# xmega-flash.net
KiCad netlist of a schematic drawn in EAGLE
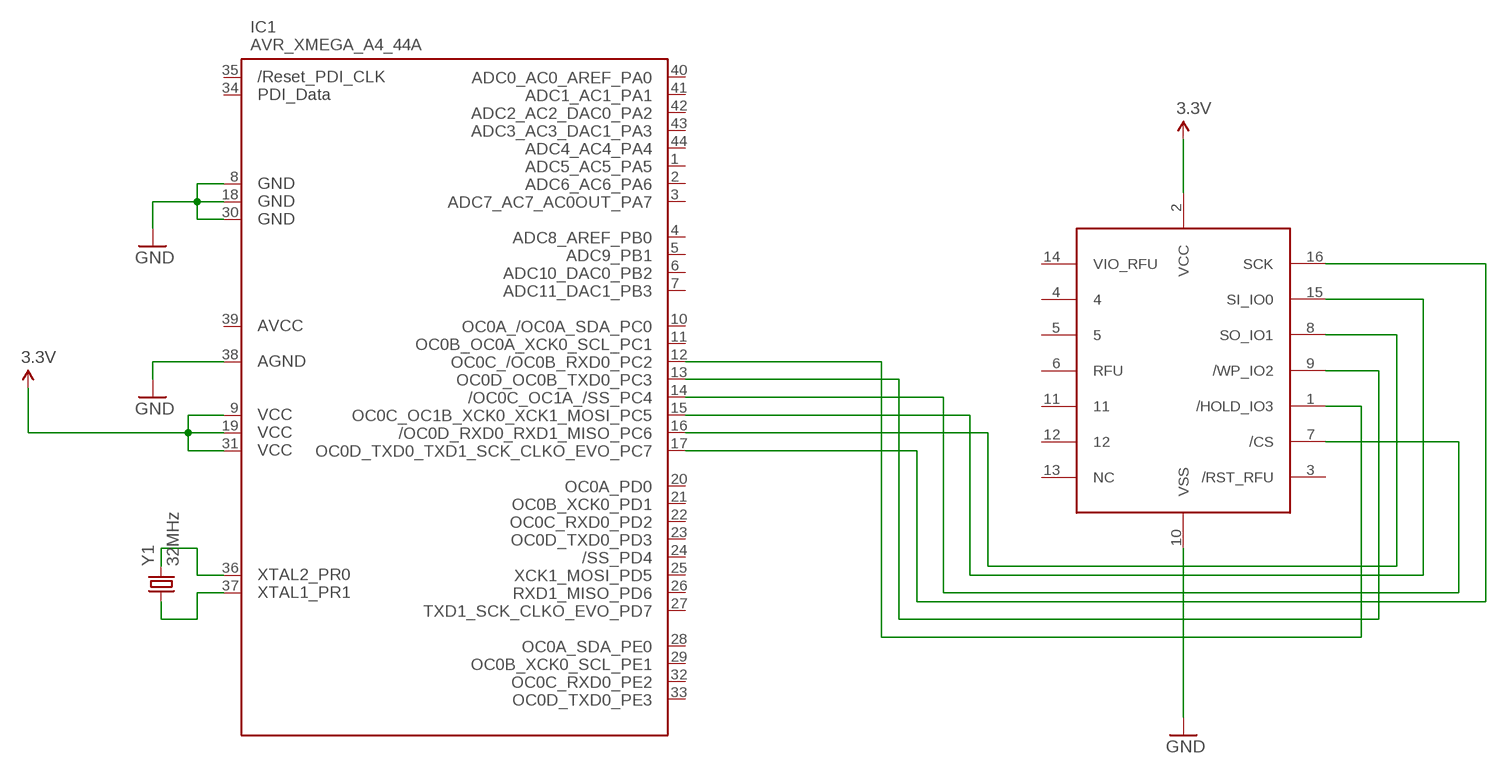
[diagram p0: schematic, sheet 1]

(export (version "E")
  (design (tool "Eeschema 10.0.6"))
  (components
    (comp (ref "IC1")
      (value "AVR_XMEGA_A4_44A")
      (footprint "eagle-import:TQFP44")
      (libsource (lib "eagle-import") (part "AVR_XMEGA_A4_44A"))
    )
    (comp (ref "U$1")
      (value "S25FLS256")
      (footprint "eagle-import:WSOIC-16")
      (libsource (lib "eagle-import") (part "S25FLS256"))
    )
    (comp (ref "Y1")
      (value "32MHz")
      (footprint "eagle-import:CRYSTAL-SMD-5X3")
      (libsource (lib "eagle-import") (part "CRYSTAL5X3"))
    )
  )
  (nets
    (net (code "1") (name "3.3V") (class "Default")
      (node (ref "IC1") (pin "19") (pinfunction "VCC2_19") (pintype "bidirectional"))
      (node (ref "IC1") (pin "31") (pinfunction "VCC3_31") (pintype "bidirectional"))
      (node (ref "IC1") (pin "9") (pinfunction "VCC1_9") (pintype "bidirectional"))
      (node (ref "U$1") (pin "2") (pinfunction "VCC_2") (pintype "bidirectional"))
    )
    (net (code "2") (name "GND") (class "Default")
      (node (ref "IC1") (pin "18") (pinfunction "GND2_18") (pintype "bidirectional"))
      (node (ref "IC1") (pin "30") (pinfunction "GND3_30") (pintype "bidirectional"))
      (node (ref "IC1") (pin "38") (pinfunction "AGND_38") (pintype "bidirectional"))
      (node (ref "IC1") (pin "8") (pinfunction "GND1_8") (pintype "bidirectional"))
      (node (ref "U$1") (pin "10") (pinfunction "VSS_10") (pintype "bidirectional"))
    )
    (net (code "3") (name "Net-(IC1-PC2)") (class "Default")
      (node (ref "IC1") (pin "12") (pinfunction "PC2_12") (pintype "bidirectional"))
      (node (ref "U$1") (pin "1") (pinfunction "/HOLD_IO3_1") (pintype "bidirectional"))
    )
    (net (code "4") (name "Net-(IC1-PC3)") (class "Default")
      (node (ref "IC1") (pin "13") (pinfunction "PC3_13") (pintype "bidirectional"))
      (node (ref "U$1") (pin "9") (pinfunction "/WP_IO2_9") (pintype "bidirectional"))
    )
    (net (code "5") (name "Net-(IC1-PC4)") (class "Default")
      (node (ref "IC1") (pin "14") (pinfunction "PC4_14") (pintype "bidirectional"))
      (node (ref "U$1") (pin "7") (pinfunction "/CS_7") (pintype "bidirectional"))
    )
    (net (code "6") (name "Net-(IC1-PC5)") (class "Default")
      (node (ref "IC1") (pin "15") (pinfunction "PC5_15") (pintype "bidirectional"))
      (node (ref "U$1") (pin "15") (pinfunction "SI_IO0_15") (pintype "bidirectional"))
    )
    (net (code "7") (name "Net-(IC1-PC6)") (class "Default")
      (node (ref "IC1") (pin "16") (pinfunction "PC6_16") (pintype "bidirectional"))
      (node (ref "U$1") (pin "8") (pinfunction "SO_IO1_8") (pintype "bidirectional"))
    )
    (net (code "8") (name "Net-(IC1-PC7)") (class "Default")
      (node (ref "IC1") (pin "17") (pinfunction "PC7_17") (pintype "bidirectional"))
      (node (ref "U$1") (pin "16") (pinfunction "SCK_16") (pintype "bidirectional"))
    )
    (net (code "9") (name "Net-(IC1-PR0)") (class "Default")
      (node (ref "IC1") (pin "36") (pinfunction "PR0_36") (pintype "bidirectional"))
      (node (ref "Y1") (pin "3") (pinfunction "2_3") (pintype "passive"))
    )
    (net (code "10") (name "Net-(IC1-PR1)") (class "Default")
      (node (ref "IC1") (pin "37") (pinfunction "PR1_37") (pintype "bidirectional"))
      (node (ref "Y1") (pin "1") (pinfunction "1_1") (pintype "passive"))
    )
    (net (code "11") (name "unconnected-(IC1-AVCC-Pad39)") (class "Default")
      (node (ref "IC1") (pin "39") (pinfunction "AVCC_39") (pintype "bidirectional"))
    )
    (net (code "12") (name "unconnected-(IC1-PA0-Pad40)") (class "Default")
      (node (ref "IC1") (pin "40") (pinfunction "PA0_40") (pintype "bidirectional"))
    )
    (net (code "13") (name "unconnected-(IC1-PA1-Pad41)") (class "Default")
      (node (ref "IC1") (pin "41") (pinfunction "PA1_41") (pintype "bidirectional"))
    )
    (net (code "14") (name "unconnected-(IC1-PA2-Pad42)") (class "Default")
      (node (ref "IC1") (pin "42") (pinfunction "PA2_42") (pintype "bidirectional"))
    )
    (net (code "15") (name "unconnected-(IC1-PA3-Pad43)") (class "Default")
      (node (ref "IC1") (pin "43") (pinfunction "PA3_43") (pintype "bidirectional"))
    )
    (net (code "16") (name "unconnected-(IC1-PA4-Pad44)") (class "Default")
      (node (ref "IC1") (pin "44") (pinfunction "PA4_44") (pintype "bidirectional"))
    )
    (net (code "17") (name "unconnected-(IC1-PA5-Pad1)") (class "Default")
      (node (ref "IC1") (pin "1") (pinfunction "PA5_1") (pintype "bidirectional"))
    )
    (net (code "18") (name "unconnected-(IC1-PA6-Pad2)") (class "Default")
      (node (ref "IC1") (pin "2") (pinfunction "PA6_2") (pintype "bidirectional"))
    )
    (net (code "19") (name "unconnected-(IC1-PA7-Pad3)") (class "Default")
      (node (ref "IC1") (pin "3") (pinfunction "PA7_3") (pintype "bidirectional"))
    )
    (net (code "20") (name "unconnected-(IC1-PB0-Pad4)") (class "Default")
      (node (ref "IC1") (pin "4") (pinfunction "PB0_4") (pintype "bidirectional"))
    )
    (net (code "21") (name "unconnected-(IC1-PB1-Pad5)") (class "Default")
      (node (ref "IC1") (pin "5") (pinfunction "PB1_5") (pintype "bidirectional"))
    )
    (net (code "22") (name "unconnected-(IC1-PB2-Pad6)") (class "Default")
      (node (ref "IC1") (pin "6") (pinfunction "PB2_6") (pintype "bidirectional"))
    )
    (net (code "23") (name "unconnected-(IC1-PB3-Pad7)") (class "Default")
      (node (ref "IC1") (pin "7") (pinfunction "PB3_7") (pintype "bidirectional"))
    )
    (net (code "24") (name "unconnected-(IC1-PC0-Pad10)") (class "Default")
      (node (ref "IC1") (pin "10") (pinfunction "PC0_10") (pintype "bidirectional"))
    )
    (net (code "25") (name "unconnected-(IC1-PC1-Pad11)") (class "Default")
      (node (ref "IC1") (pin "11") (pinfunction "PC1_11") (pintype "bidirectional"))
    )
    (net (code "26") (name "unconnected-(IC1-PD0-Pad20)") (class "Default")
      (node (ref "IC1") (pin "20") (pinfunction "PD0_20") (pintype "bidirectional"))
    )
    (net (code "27") (name "unconnected-(IC1-PD1-Pad21)") (class "Default")
      (node (ref "IC1") (pin "21") (pinfunction "PD1_21") (pintype "bidirectional"))
    )
    (net (code "28") (name "unconnected-(IC1-PD2-Pad22)") (class "Default")
      (node (ref "IC1") (pin "22") (pinfunction "PD2_22") (pintype "bidirectional"))
    )
    (net (code "29") (name "unconnected-(IC1-PD3-Pad23)") (class "Default")
      (node (ref "IC1") (pin "23") (pinfunction "PD3_23") (pintype "bidirectional"))
    )
    (net (code "30") (name "unconnected-(IC1-PD4-Pad24)") (class "Default")
      (node (ref "IC1") (pin "24") (pinfunction "PD4_24") (pintype "bidirectional"))
    )
    (net (code "31") (name "unconnected-(IC1-PD5-Pad25)") (class "Default")
      (node (ref "IC1") (pin "25") (pinfunction "PD5_25") (pintype "bidirectional"))
    )
    (net (code "32") (name "unconnected-(IC1-PD6-Pad26)") (class "Default")
      (node (ref "IC1") (pin "26") (pinfunction "PD6_26") (pintype "bidirectional"))
    )
    (net (code "33") (name "unconnected-(IC1-PD7-Pad27)") (class "Default")
      (node (ref "IC1") (pin "27") (pinfunction "PD7_27") (pintype "bidirectional"))
    )
    (net (code "34") (name "unconnected-(IC1-PDI_DATA-Pad34)") (class "Default")
      (node (ref "IC1") (pin "34") (pinfunction "PDI_DATA_34") (pintype "bidirectional"))
    )
    (net (code "35") (name "unconnected-(IC1-PE0-Pad28)") (class "Default")
      (node (ref "IC1") (pin "28") (pinfunction "PE0_28") (pintype "bidirectional"))
    )
    (net (code "36") (name "unconnected-(IC1-PE1-Pad29)") (class "Default")
      (node (ref "IC1") (pin "29") (pinfunction "PE1_29") (pintype "bidirectional"))
    )
    (net (code "37") (name "unconnected-(IC1-PE2-Pad32)") (class "Default")
      (node (ref "IC1") (pin "32") (pinfunction "PE2_32") (pintype "bidirectional"))
    )
    (net (code "38") (name "unconnected-(IC1-PE3-Pad33)") (class "Default")
      (node (ref "IC1") (pin "33") (pinfunction "PE3_33") (pintype "bidirectional"))
    )
    (net (code "39") (name "unconnected-(IC1-RESET-Pad35)") (class "Default")
      (node (ref "IC1") (pin "35") (pinfunction "RESET_35") (pintype "bidirectional"))
    )
    (net (code "40") (name "unconnected-(U$1-NC-Pad13)") (class "Default")
      (node (ref "U$1") (pin "13") (pinfunction "NC_13") (pintype "bidirectional"))
    )
    (net (code "41") (name "unconnected-(U$1-Pad4)") (class "Default")
      (node (ref "U$1") (pin "4") (pinfunction "4_4") (pintype "bidirectional"))
    )
    (net (code "42") (name "unconnected-(U$1-Pad5)") (class "Default")
      (node (ref "U$1") (pin "5") (pinfunction "5_5") (pintype "bidirectional"))
    )
    (net (code "43") (name "unconnected-(U$1-Pad11)") (class "Default")
      (node (ref "U$1") (pin "11") (pinfunction "11_11") (pintype "bidirectional"))
    )
    (net (code "44") (name "unconnected-(U$1-Pad12)") (class "Default")
      (node (ref "U$1") (pin "12") (pinfunction "12_12") (pintype "bidirectional"))
    )
    (net (code "45") (name "unconnected-(U$1-RFU-Pad6)") (class "Default")
      (node (ref "U$1") (pin "6") (pinfunction "RFU_6") (pintype "bidirectional"))
    )
    (net (code "46") (name "unconnected-(U$1-VIO_RFU-Pad14)") (class "Default")
      (node (ref "U$1") (pin "14") (pinfunction "VIO_RFU_14") (pintype "bidirectional"))
    )
    (net (code "47") (name "unconnected-(U$1-{slash}RST_RFU-Pad3)") (class "Default")
      (node (ref "U$1") (pin "3") (pinfunction "/RST_RFU_3") (pintype "bidirectional"))
    )
  )
)
